# Connectors.net
KiCad netlist of a schematic drawn in Altium Designer
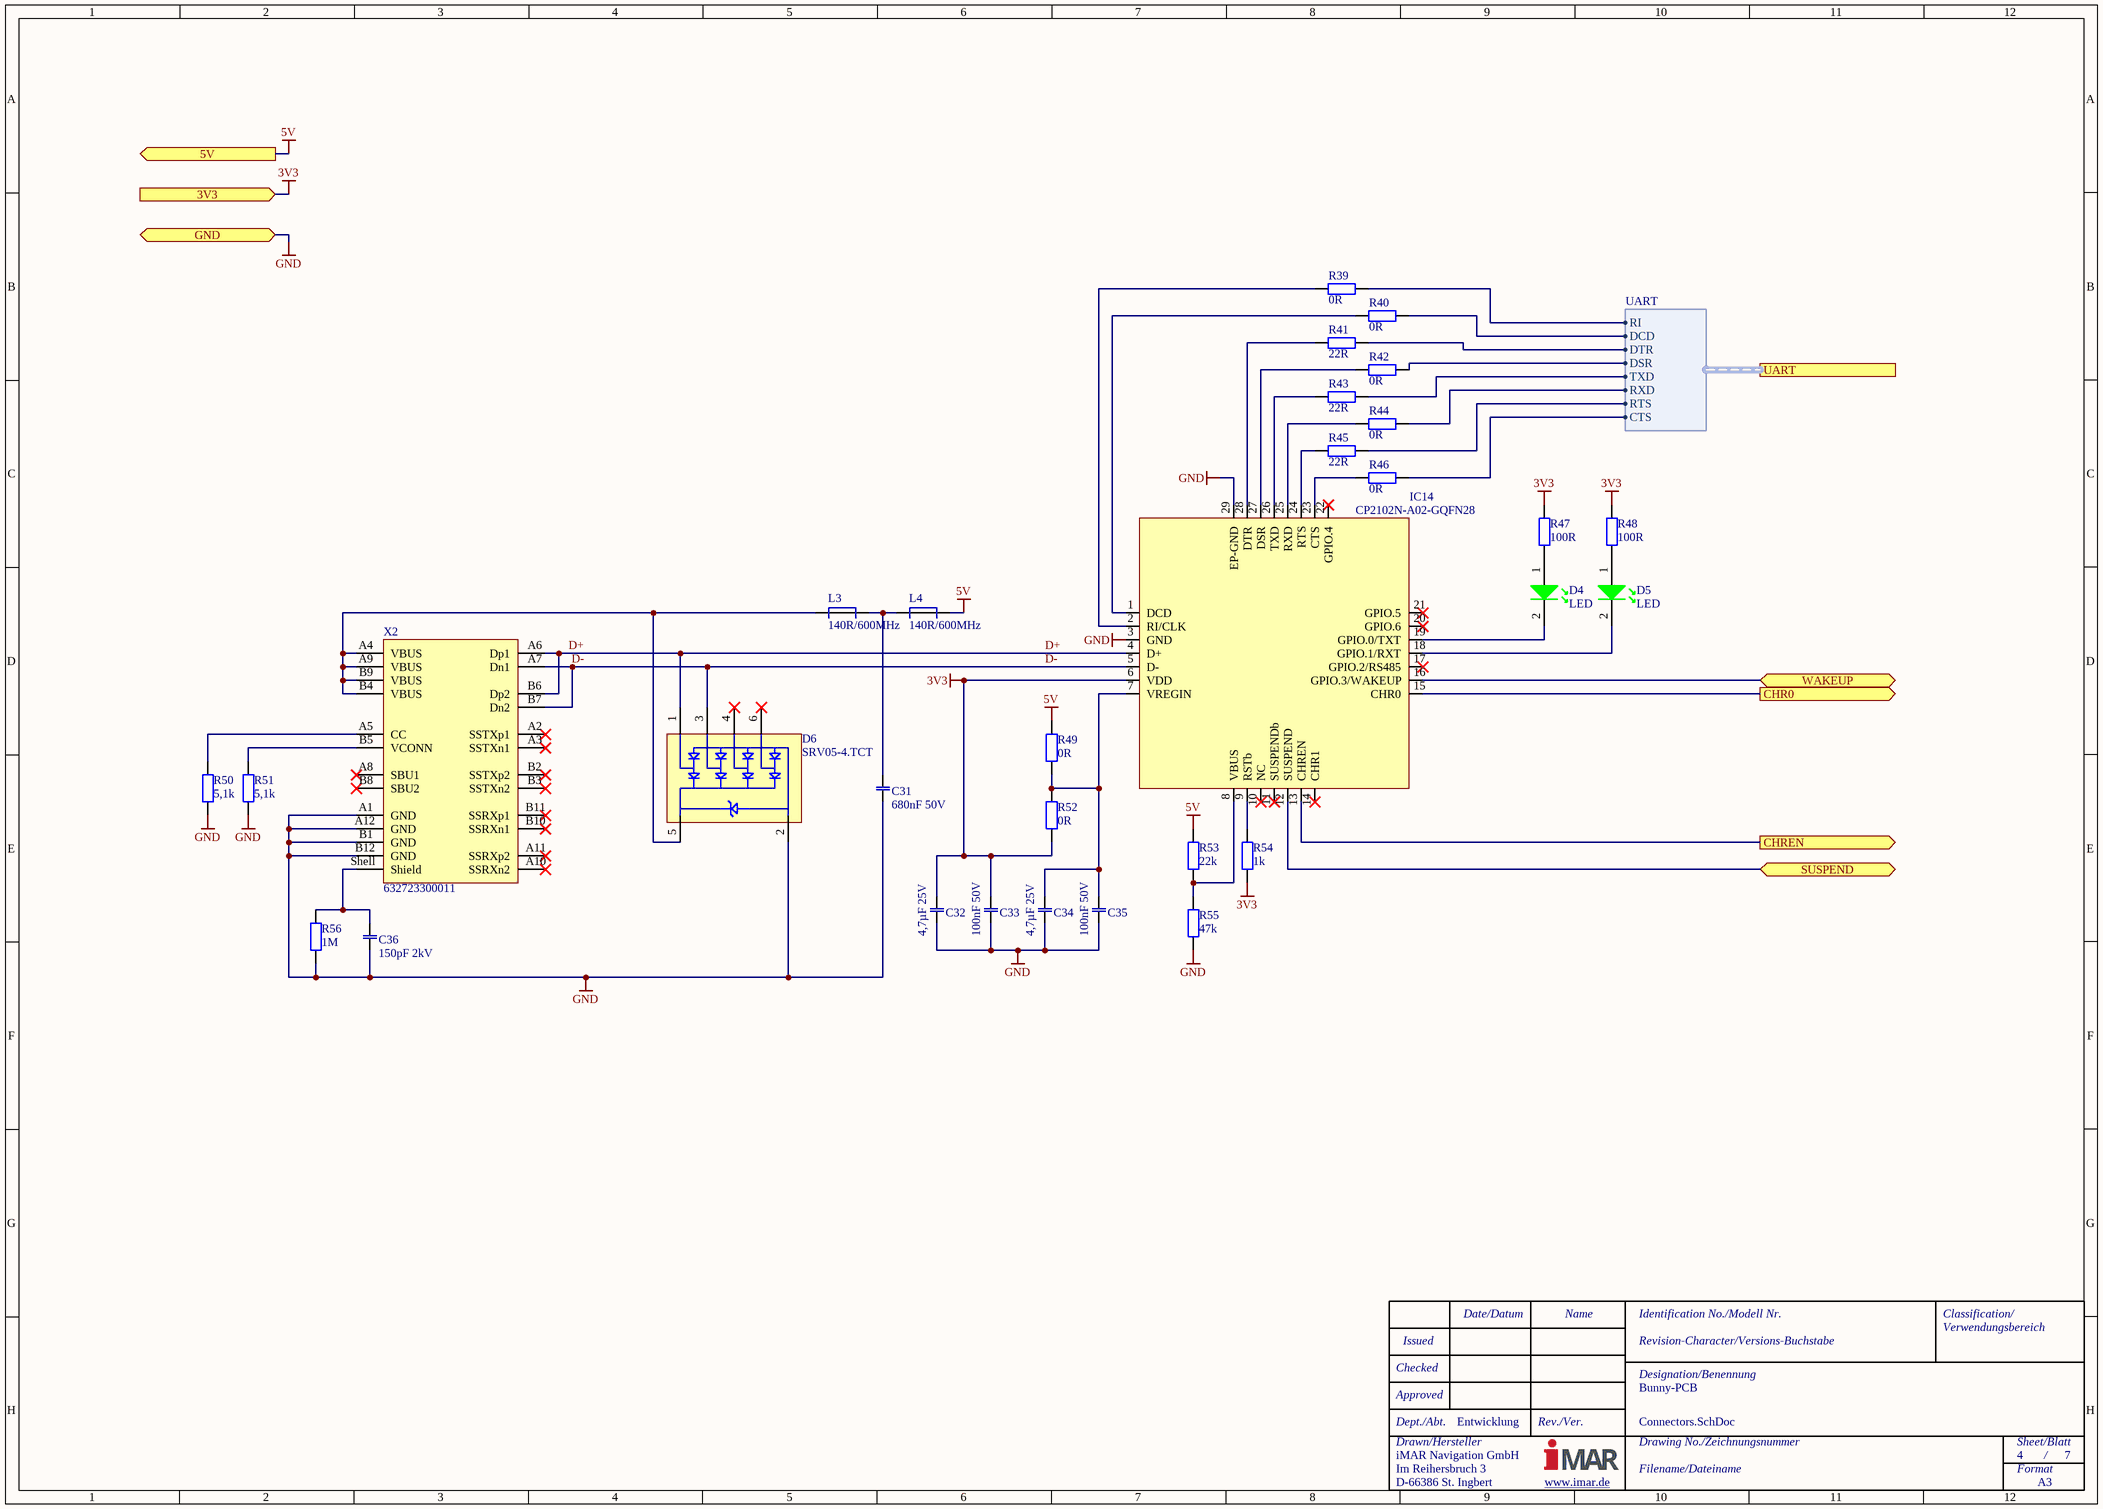
[diagram p0: Connectors.SchDoc]

(export (version "E")
  (design (tool "Eeschema 10.0.6"))
  (components
    (comp (ref "C31")
      (value "680nF 50V")
      (footprint "CAPC1608L")
      (description "680nF  50V  Ceramic  0603  10%  X5R")
      (fields (field (name "VOLTAGE") "50V") (field (name "TOLERANCE") "10%"))
      (libsource (lib "iMAR Workspace") (part "Kondensator"))
    )
    (comp (ref "C32")
      (value "4,7µF 25V")
      (footprint "CAPC1608L")
      (description "4,7µF  25V  Ceramic  0603  10%  X5R")
      (fields (field (name "MANUFACTURER") "unspecified") (field (name "VOLTAGE") "25V"))
      (libsource (lib "iMAR Workspace") (part "Kondensator"))
    )
    (comp (ref "C33")
      (value "100nF 50V")
      (footprint "CAPC1005N")
      (description "100nF  50V  Ceramic  0402  10%  X7R")
      (fields (field (name "VOLTAGE") "50V") (field (name "MANUFACTURER") "unspecified"))
      (libsource (lib "iMAR Workspace") (part "Kondensator"))
    )
    (comp (ref "C34")
      (value "4,7µF 25V")
      (footprint "CAPC1608L")
      (description "4,7µF  25V  Ceramic  0603  10%  X5R")
      (fields (field (name "MANUFACTURER") "unspecified") (field (name "VOLTAGE") "25V"))
      (libsource (lib "iMAR Workspace") (part "Kondensator"))
    )
    (comp (ref "C35")
      (value "100nF 50V")
      (footprint "CAPC1005N")
      (description "100nF  50V  Ceramic  0402  10%  X7R")
      (fields (field (name "VOLTAGE") "50V") (field (name "MANUFACTURER") "unspecified"))
      (libsource (lib "iMAR Workspace") (part "Kondensator"))
    )
    (comp (ref "C36")
      (value "150pF 2kV")
      (footprint "CAPC3216L")
      (description "150pF  2kV  Ceramic  1206  10%  X7R")
      (fields (field (name "MANUFACTURER") "unspecified") (field (name "TOLERANCE") "10%"))
      (libsource (lib "iMAR Workspace") (part "Kondensator"))
    )
    (comp (ref "D4")
      (value "LED")
      (footprint "LEDM1608X11_Green")
      (description "LED green 0603 2,2V 20mA")
      (fields (field (name "MANUFACTURER") "KINGBRIGHT") (field (name "POWER") "62.5mW"))
      (libsource (lib "iMAR Workspace") (part "LED green"))
    )
    (comp (ref "D5")
      (value "LED")
      (footprint "LEDM1608X11_Green")
      (description "LED green 0603 2,2V 20mA")
      (fields (field (name "MANUFACTURER") "KINGBRIGHT") (field (name "POWER") "62.5mW"))
      (libsource (lib "iMAR Workspace") (part "LED green"))
    )
    (comp (ref "D6")
      (value "SRV05-4.TCT")
      (footprint "SOT95P280X110-6N")
      (description "Low Capacitance TVS Diode Array,USB, 10/100/1000 ETH")
      (fields (field (name "MANUFACTURER") "SEMTECH") (field (name "POWER") "300W"))
      (libsource (lib "iMAR Workspace") (part "SRV05-4A"))
    )
    (comp (ref "IC14")
      (value "CP2102N-A02-GQFN28")
      (footprint "QFN50P500X500X80_HS-29N")
      (description "USB-IC-Schnittstelle USBXpress - USB to UART Bridge")
      (fields (field (name "MANUFACTURER") "SILICON LABS"))
      (libsource (lib "iMAR Workspace") (part "CP2102N-A02-GQFN28"))
    )
    (comp (ref "L3")
      (value "140R/600MHz")
      (footprint "INDC1005X06N")
      (description "140R/600MHz  1,2A  0402  WE-CBF SMD EMI Suppression Ferrite Bead")
      (fields (field (name "MANUFACTURER") "WUERTH ELEKTRONIK"))
      (libsource (lib "iMAR Workspace") (part "Ferrit-Perle"))
    )
    (comp (ref "L4")
      (value "140R/600MHz")
      (footprint "INDC1005X06N")
      (description "140R/600MHz  1,2A  0402  WE-CBF SMD EMI Suppression Ferrite Bead")
      (fields (field (name "MANUFACTURER") "WUERTH ELEKTRONIK"))
      (libsource (lib "iMAR Workspace") (part "Ferrit-Perle"))
    )
    (comp (ref "R39")
      (value "0R")
      (footprint "RESC1005L")
      (description "0R  0402  0mW  0%  0ppm  0V")
      (fields (field (name "VOLTAGE") "0V") (field (name "TOLERANCE") "0%"))
      (libsource (lib "") (part "Widerstand_2"))
    )
    (comp (ref "R40")
      (value "0R")
      (footprint "RESC1005L")
      (description "0R  0402  0mW  0%  0ppm  0V")
      (fields (field (name "VOLTAGE") "0V") (field (name "TOLERANCE") "0%"))
      (libsource (lib "") (part "Widerstand_2"))
    )
    (comp (ref "R41")
      (value "22R")
      (footprint "RESC1005L")
      (description "22R  0402  62mW  1%  100ppm  50V")
      (fields (field (name "MANUFACTURER") "unspecified") (field (name "POWER") "62mW"))
      (libsource (lib "") (part "Widerstand_3"))
    )
    (comp (ref "R42")
      (value "0R")
      (footprint "RESC1005L")
      (description "0R  0402  0mW  0%  0ppm  0V")
      (fields (field (name "VOLTAGE") "0V") (field (name "TOLERANCE") "0%"))
      (libsource (lib "") (part "Widerstand_2"))
    )
    (comp (ref "R43")
      (value "22R")
      (footprint "RESC1005L")
      (description "22R  0402  62mW  1%  100ppm  50V")
      (fields (field (name "MANUFACTURER") "unspecified") (field (name "POWER") "62mW"))
      (libsource (lib "") (part "Widerstand_2"))
    )
    (comp (ref "R44")
      (value "0R")
      (footprint "RESC1005L")
      (description "0R  0402  0mW  0%  0ppm  0V")
      (fields (field (name "VOLTAGE") "0V") (field (name "TOLERANCE") "0%"))
      (libsource (lib "") (part "Widerstand_2"))
    )
    (comp (ref "R45")
      (value "22R")
      (footprint "RESC1005L")
      (description "22R  0402  62mW  1%  100ppm  50V")
      (fields (field (name "MANUFACTURER") "unspecified") (field (name "POWER") "62mW"))
      (libsource (lib "") (part "Widerstand_3"))
    )
    (comp (ref "R46")
      (value "0R")
      (footprint "RESC1005L")
      (description "0R  0402  0mW  0%  0ppm  0V")
      (fields (field (name "VOLTAGE") "0V") (field (name "TOLERANCE") "0%"))
      (libsource (lib "") (part "Widerstand_2"))
    )
    (comp (ref "R47")
      (value "100R")
      (footprint "RESC1005L")
      (description "100R  0402  62mW  1%  100ppm  50V")
      (fields (field (name "TOLERANCE") "1%") (field (name "POWER") "62mW"))
      (libsource (lib "") (part "Widerstand_1"))
    )
    (comp (ref "R48")
      (value "100R")
      (footprint "RESC1005L")
      (description "100R  0402  62mW  1%  100ppm  50V")
      (fields (field (name "TOLERANCE") "1%") (field (name "POWER") "62mW"))
      (libsource (lib "") (part "Widerstand_1"))
    )
    (comp (ref "R49")
      (value "0R")
      (footprint "RESC1005L")
      (description "0R  0402  0mW  0%  0ppm  0V")
      (fields (field (name "VOLTAGE") "0V") (field (name "TOLERANCE") "0%"))
      (libsource (lib "") (part "Widerstand_1"))
    )
    (comp (ref "R50")
      (value "5,1k")
      (footprint "RESC1005L")
      (description "5,1k  0402  62mW  1%  100ppm  50V")
      (fields (field (name "MANUFACTURER") "unspecified") (field (name "VOLTAGE") "50V"))
      (libsource (lib "") (part "Widerstand_1"))
    )
    (comp (ref "R51")
      (value "5,1k")
      (footprint "RESC1005L")
      (description "5,1k  0402  62mW  1%  100ppm  50V")
      (fields (field (name "MANUFACTURER") "unspecified") (field (name "VOLTAGE") "50V"))
      (libsource (lib "") (part "Widerstand_1"))
    )
    (comp (ref "R52")
      (value "0R")
      (footprint "RESC1005L")
      (description "0R  0402  0mW  0%  0ppm  0V")
      (fields (field (name "VOLTAGE") "0V") (field (name "TOLERANCE") "0%"))
      (libsource (lib "iMAR Workspace") (part "Widerstand"))
    )
    (comp (ref "R53")
      (value "22k")
      (footprint "RESC1005L")
      (description "22k  0402  62mW  1%  100ppm  50V")
      (fields (field (name "VOLTAGE") "50V") (field (name "MANUFACTURER") "unspecified"))
      (libsource (lib "") (part "Widerstand_1"))
    )
    (comp (ref "R54")
      (value "1k")
      (footprint "RESC1005L")
      (description "1k  0402  62mW  1%  100ppm  50V")
      (fields (field (name "POWER") "62mW") (field (name "TOLERANCE") "1%"))
      (libsource (lib "") (part "Widerstand_1"))
    )
    (comp (ref "R55")
      (value "47k")
      (footprint "RESC1005L")
      (description "47k  0402  62mW  1%  100ppm  50V")
      (fields (field (name "MANUFACTURER") "unspecified") (field (name "POWER") "62mW"))
      (libsource (lib "") (part "Widerstand_1"))
    )
    (comp (ref "R56")
      (value "1M")
      (footprint "RESC2012L")
      (description "1M  0805  125mW  1%  100ppm  150V")
      (fields (field (name "MANUFACTURER") "unspecified") (field (name "POWER") "125mW"))
      (libsource (lib "") (part "Widerstand_1"))
    )
    (comp (ref "X2")
      (value "632723300011")
      (footprint "WE_632723300011")
      (description "WR-COM USB 3.1 Type C Receptacle Horizontal THR / SMT")
      (fields (field (name "MANUFACTURER") "WUERTH ELEKTRONIK"))
      (libsource (lib "iMAR Workspace") (part "632722110112"))
    )
  )
  (nets
    (net (code "2") (name "/CHR0") (class "Default")
      (node (ref "IC14") (pin "15") (pinfunction "CHR0_15") (pintype "passive"))
    )
    (net (code "3") (name "/CHREN") (class "Default")
      (node (ref "IC14") (pin "13") (pinfunction "CHREN_13") (pintype "passive"))
    )
    (net (code "4") (name "/CTS") (class "Default")
      (node (ref "R46") (pin "2") (pinfunction "2_2") (pintype "passive"))
    )
    (net (code "5") (name "/D+") (class "Default")
      (node (ref "D6") (pin "1") (pinfunction "1_1") (pintype "passive"))
      (node (ref "IC14") (pin "4") (pinfunction "D+_4") (pintype "passive"))
      (node (ref "X2") (pin "A6") (pinfunction "Dp1_A6") (pintype "passive"))
      (node (ref "X2") (pin "B6") (pinfunction "Dp2_B6") (pintype "passive"))
    )
    (net (code "6") (name "/D-") (class "Default")
      (node (ref "D6") (pin "3") (pinfunction "3_3") (pintype "passive"))
      (node (ref "IC14") (pin "5") (pinfunction "D-_5") (pintype "passive"))
      (node (ref "X2") (pin "A7") (pinfunction "Dn1_A7") (pintype "passive"))
      (node (ref "X2") (pin "B7") (pinfunction "Dn2_B7") (pintype "passive"))
    )
    (net (code "7") (name "/DCD") (class "Default")
      (node (ref "R40") (pin "2") (pinfunction "2_2") (pintype "passive"))
    )
    (net (code "8") (name "/DSR") (class "Default")
      (node (ref "R42") (pin "2") (pinfunction "2_2") (pintype "passive"))
    )
    (net (code "9") (name "/DTR") (class "Default")
      (node (ref "R41") (pin "1") (pinfunction "1_1") (pintype "passive"))
    )
    (net (code "10") (name "/RI") (class "Default")
      (node (ref "R39") (pin "2") (pinfunction "2_2") (pintype "passive"))
    )
    (net (code "11") (name "/RTS") (class "Default")
      (node (ref "R45") (pin "1") (pinfunction "1_1") (pintype "passive"))
    )
    (net (code "12") (name "/RXD") (class "Default")
      (node (ref "R44") (pin "2") (pinfunction "2_2") (pintype "passive"))
    )
    (net (code "13") (name "/SUSPEND") (class "Default")
      (node (ref "IC14") (pin "12") (pinfunction "SUSPEND_12") (pintype "passive"))
    )
    (net (code "14") (name "/TXD") (class "Default")
      (node (ref "R43") (pin "2") (pinfunction "2_2") (pintype "passive"))
    )
    (net (code "15") (name "/WAKEUP") (class "Default")
      (node (ref "IC14") (pin "16") (pinfunction "GPIO.3/WAKEUP_16") (pintype "passive"))
    )
    (net (code "17") (name "3V3") (class "Default")
      (node (ref "C32") (pin "2") (pinfunction "2_2") (pintype "passive"))
      (node (ref "C33") (pin "2") (pinfunction "2_2") (pintype "passive"))
      (node (ref "IC14") (pin "6") (pinfunction "VDD_6") (pintype "passive"))
      (node (ref "R47") (pin "2") (pinfunction "2_2") (pintype "passive"))
      (node (ref "R48") (pin "2") (pinfunction "2_2") (pintype "passive"))
      (node (ref "R52") (pin "2") (pinfunction "2_2") (pintype "passive"))
      (node (ref "R54") (pin "1") (pinfunction "1_1") (pintype "passive"))
    )
    (net (code "18") (name "5V") (class "Default")
      (node (ref "L4") (pin "2") (pinfunction "2_2") (pintype "passive"))
      (node (ref "R49") (pin "2") (pinfunction "2_2") (pintype "passive"))
      (node (ref "R53") (pin "2") (pinfunction "2_2") (pintype "passive"))
    )
    (net (code "19") (name "GND") (class "Default")
      (node (ref "C31") (pin "1") (pinfunction "1_1") (pintype "passive"))
      (node (ref "C32") (pin "1") (pinfunction "1_1") (pintype "passive"))
      (node (ref "C33") (pin "1") (pinfunction "1_1") (pintype "passive"))
      (node (ref "C34") (pin "1") (pinfunction "1_1") (pintype "passive"))
      (node (ref "C35") (pin "1") (pinfunction "1_1") (pintype "passive"))
      (node (ref "C36") (pin "1") (pinfunction "1_1") (pintype "passive"))
      (node (ref "D6") (pin "2") (pinfunction "2_2") (pintype "passive"))
      (node (ref "IC14") (pin "29") (pinfunction "EP-GND_29") (pintype "passive"))
      (node (ref "IC14") (pin "3") (pinfunction "GND_3") (pintype "passive"))
      (node (ref "R50") (pin "1") (pinfunction "1_1") (pintype "passive"))
      (node (ref "R51") (pin "1") (pinfunction "1_1") (pintype "passive"))
      (node (ref "R55") (pin "1") (pinfunction "1_1") (pintype "passive"))
      (node (ref "R56") (pin "1") (pinfunction "1_1") (pintype "passive"))
      (node (ref "X2") (pin "A1") (pinfunction "GND_A1") (pintype "passive"))
      (node (ref "X2") (pin "A12") (pinfunction "GND_A12") (pintype "passive"))
      (node (ref "X2") (pin "B1") (pinfunction "GND_B1") (pintype "passive"))
      (node (ref "X2") (pin "B12") (pinfunction "GND_B12") (pintype "passive"))
    )
    (net (code "20") (name "Net-(C31-Pad2)") (class "Default")
      (node (ref "C31") (pin "2") (pinfunction "2_2") (pintype "passive"))
      (node (ref "L3") (pin "2") (pinfunction "2_2") (pintype "passive"))
      (node (ref "L4") (pin "1") (pinfunction "1_1") (pintype "passive"))
    )
    (net (code "21") (name "Net-(D4-Pad1)") (class "Default")
      (node (ref "D4") (pin "1") (pinfunction "1_1") (pintype "passive"))
      (node (ref "R47") (pin "1") (pinfunction "1_1") (pintype "passive"))
    )
    (net (code "22") (name "Net-(D5-Pad1)") (class "Default")
      (node (ref "D5") (pin "1") (pinfunction "1_1") (pintype "passive"))
      (node (ref "R48") (pin "1") (pinfunction "1_1") (pintype "passive"))
    )
    (net (code "23") (name "Net-(D6-Pad5)") (class "Default")
      (node (ref "D6") (pin "5") (pinfunction "5_5") (pintype "passive"))
      (node (ref "L3") (pin "1") (pinfunction "1_1") (pintype "passive"))
      (node (ref "X2") (pin "A4") (pinfunction "VBUS_A4") (pintype "passive"))
      (node (ref "X2") (pin "A9") (pinfunction "VBUS_A9") (pintype "passive"))
      (node (ref "X2") (pin "B4") (pinfunction "VBUS_B4") (pintype "passive"))
      (node (ref "X2") (pin "B9") (pinfunction "VBUS_B9") (pintype "passive"))
    )
    (net (code "24") (name "Net-(IC14-CTS)") (class "Default")
      (node (ref "IC14") (pin "23") (pinfunction "CTS_23") (pintype "passive"))
      (node (ref "R46") (pin "1") (pinfunction "1_1") (pintype "passive"))
    )
    (net (code "25") (name "Net-(IC14-DCD)") (class "Default")
      (node (ref "IC14") (pin "1") (pinfunction "DCD_1") (pintype "passive"))
      (node (ref "R40") (pin "1") (pinfunction "1_1") (pintype "passive"))
    )
    (net (code "26") (name "Net-(IC14-DSR)") (class "Default")
      (node (ref "IC14") (pin "27") (pinfunction "DSR_27") (pintype "passive"))
      (node (ref "R42") (pin "1") (pinfunction "1_1") (pintype "passive"))
    )
    (net (code "27") (name "Net-(IC14-DTR)") (class "Default")
      (node (ref "IC14") (pin "28") (pinfunction "DTR_28") (pintype "passive"))
      (node (ref "R41") (pin "2") (pinfunction "2_2") (pintype "passive"))
    )
    (net (code "28") (name "Net-(IC14-GPIO.0{slash}TXT)") (class "Default")
      (node (ref "D4") (pin "2") (pinfunction "2_2") (pintype "passive"))
      (node (ref "IC14") (pin "19") (pinfunction "GPIO.0/TXT_19") (pintype "passive"))
    )
    (net (code "29") (name "Net-(IC14-GPIO.1{slash}RXT)") (class "Default")
      (node (ref "D5") (pin "2") (pinfunction "2_2") (pintype "passive"))
      (node (ref "IC14") (pin "18") (pinfunction "GPIO.1/RXT_18") (pintype "passive"))
    )
    (net (code "30") (name "Net-(IC14-RI{slash}CLK)") (class "Default")
      (node (ref "IC14") (pin "2") (pinfunction "RI/CLK_2") (pintype "passive"))
      (node (ref "R39") (pin "1") (pinfunction "1_1") (pintype "passive"))
    )
    (net (code "31") (name "Net-(IC14-RSTb)") (class "Default")
      (node (ref "IC14") (pin "9") (pinfunction "RSTb_9") (pintype "passive"))
      (node (ref "R54") (pin "2") (pinfunction "2_2") (pintype "passive"))
    )
    (net (code "32") (name "Net-(IC14-RTS)") (class "Default")
      (node (ref "IC14") (pin "24") (pinfunction "RTS_24") (pintype "passive"))
      (node (ref "R45") (pin "2") (pinfunction "2_2") (pintype "passive"))
    )
    (net (code "33") (name "Net-(IC14-RXD)") (class "Default")
      (node (ref "IC14") (pin "25") (pinfunction "RXD_25") (pintype "passive"))
      (node (ref "R44") (pin "1") (pinfunction "1_1") (pintype "passive"))
    )
    (net (code "34") (name "Net-(IC14-TXD)") (class "Default")
      (node (ref "IC14") (pin "26") (pinfunction "TXD_26") (pintype "passive"))
      (node (ref "R43") (pin "1") (pinfunction "1_1") (pintype "passive"))
    )
    (net (code "35") (name "Net-(IC14-VBUS)") (class "Default")
      (node (ref "IC14") (pin "8") (pinfunction "VBUS_8") (pintype "passive"))
      (node (ref "R53") (pin "1") (pinfunction "1_1") (pintype "passive"))
      (node (ref "R55") (pin "2") (pinfunction "2_2") (pintype "passive"))
    )
    (net (code "36") (name "Net-(IC14-VREGIN)") (class "Default")
      (node (ref "C34") (pin "2") (pinfunction "2_2") (pintype "passive"))
      (node (ref "C35") (pin "2") (pinfunction "2_2") (pintype "passive"))
      (node (ref "IC14") (pin "7") (pinfunction "VREGIN_7") (pintype "passive"))
      (node (ref "R49") (pin "1") (pinfunction "1_1") (pintype "passive"))
      (node (ref "R52") (pin "1") (pinfunction "1_1") (pintype "passive"))
    )
    (net (code "37") (name "Net-(X2-CC)") (class "Default")
      (node (ref "R50") (pin "2") (pinfunction "2_2") (pintype "passive"))
      (node (ref "X2") (pin "A5") (pinfunction "CC_A5") (pintype "passive"))
    )
    (net (code "38") (name "Net-(X2-Shield)") (class "Default")
      (node (ref "C36") (pin "2") (pinfunction "2_2") (pintype "passive"))
      (node (ref "R56") (pin "2") (pinfunction "2_2") (pintype "passive"))
      (node (ref "X2") (pin "Shell") (pinfunction "Shield_Shell") (pintype "passive"))
    )
    (net (code "39") (name "Net-(X2-VCONN)") (class "Default")
      (node (ref "R51") (pin "2") (pinfunction "2_2") (pintype "passive"))
      (node (ref "X2") (pin "B5") (pinfunction "VCONN_B5") (pintype "passive"))
    )
    (net (code "40") (name "unconnected-(D6-Pad4)") (class "Default")
      (node (ref "D6") (pin "4") (pinfunction "4_4") (pintype "passive+no_connect"))
    )
    (net (code "41") (name "unconnected-(D6-Pad6)") (class "Default")
      (node (ref "D6") (pin "6") (pinfunction "6_6") (pintype "passive+no_connect"))
    )
    (net (code "42") (name "unconnected-(IC14-CHR1-Pad14)") (class "Default")
      (node (ref "IC14") (pin "14") (pinfunction "CHR1_14") (pintype "passive+no_connect"))
    )
    (net (code "43") (name "unconnected-(IC14-GPIO.2{slash}RS485-Pad17)") (class "Default")
      (node (ref "IC14") (pin "17") (pinfunction "GPIO.2/RS485_17") (pintype "passive+no_connect"))
    )
    (net (code "44") (name "unconnected-(IC14-GPIO.4-Pad22)") (class "Default")
      (node (ref "IC14") (pin "22") (pinfunction "GPIO.4_22") (pintype "passive+no_connect"))
    )
    (net (code "45") (name "unconnected-(IC14-GPIO.5-Pad21)") (class "Default")
      (node (ref "IC14") (pin "21") (pinfunction "GPIO.5_21") (pintype "passive+no_connect"))
    )
    (net (code "46") (name "unconnected-(IC14-GPIO.6-Pad20)") (class "Default")
      (node (ref "IC14") (pin "20") (pinfunction "GPIO.6_20") (pintype "passive+no_connect"))
    )
    (net (code "47") (name "unconnected-(IC14-NC-Pad10)") (class "Default")
      (node (ref "IC14") (pin "10") (pinfunction "NC_10") (pintype "passive+no_connect"))
    )
    (net (code "48") (name "unconnected-(IC14-SUSPENDb-Pad11)") (class "Default")
      (node (ref "IC14") (pin "11") (pinfunction "SUSPENDb_11") (pintype "passive+no_connect"))
    )
    (net (code "49") (name "unconnected-(X2-SBU1-PadA8)") (class "Default")
      (node (ref "X2") (pin "A8") (pinfunction "SBU1_A8") (pintype "passive+no_connect"))
    )
    (net (code "50") (name "unconnected-(X2-SBU2-PadB8)") (class "Default")
      (node (ref "X2") (pin "B8") (pinfunction "SBU2_B8") (pintype "passive+no_connect"))
    )
    (net (code "51") (name "unconnected-(X2-SSRXn1-PadB10)") (class "Default")
      (node (ref "X2") (pin "B10") (pinfunction "SSRXn1_B10") (pintype "passive+no_connect"))
    )
    (net (code "52") (name "unconnected-(X2-SSRXn2-PadA10)") (class "Default")
      (node (ref "X2") (pin "A10") (pinfunction "SSRXn2_A10") (pintype "passive+no_connect"))
    )
    (net (code "53") (name "unconnected-(X2-SSRXp1-PadB11)") (class "Default")
      (node (ref "X2") (pin "B11") (pinfunction "SSRXp1_B11") (pintype "passive+no_connect"))
    )
    (net (code "54") (name "unconnected-(X2-SSRXp2-PadA11)") (class "Default")
      (node (ref "X2") (pin "A11") (pinfunction "SSRXp2_A11") (pintype "passive+no_connect"))
    )
    (net (code "55") (name "unconnected-(X2-SSTXn1-PadA3)") (class "Default")
      (node (ref "X2") (pin "A3") (pinfunction "SSTXn1_A3") (pintype "passive+no_connect"))
    )
    (net (code "56") (name "unconnected-(X2-SSTXn2-PadB3)") (class "Default")
      (node (ref "X2") (pin "B3") (pinfunction "SSTXn2_B3") (pintype "passive+no_connect"))
    )
    (net (code "57") (name "unconnected-(X2-SSTXp1-PadA2)") (class "Default")
      (node (ref "X2") (pin "A2") (pinfunction "SSTXp1_A2") (pintype "passive+no_connect"))
    )
    (net (code "58") (name "unconnected-(X2-SSTXp2-PadB2)") (class "Default")
      (node (ref "X2") (pin "B2") (pinfunction "SSTXp2_B2") (pintype "passive+no_connect"))
    )
  )
)
